# mic_v3.net
KiCad netlist of a schematic drawn in EAGLE
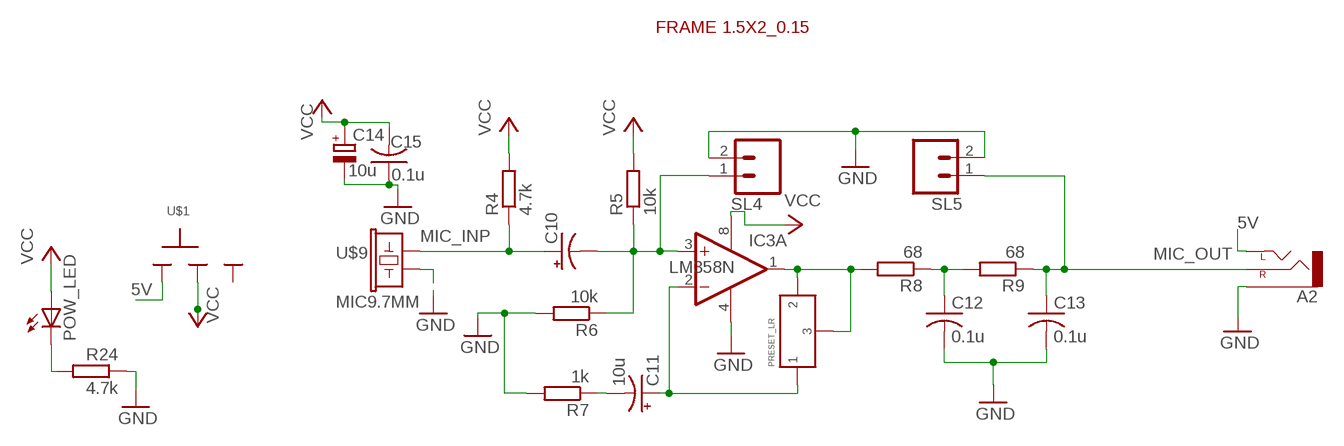
[diagram p0: schematic, sheet 1]

(export (version "E")
  (design (tool "Eeschema 10.0.6"))
  (components
    (comp (ref "A2")
      (value "AUDIO-JACKPTH")
      (footprint "eagle-import:AUDIO-JACK")
      (libsource (lib "eagle-import") (part "AUDIO-JACKPTH"))
    )
    (comp (ref "C10")
      (value "CPOL-USE2.5-5")
      (footprint "eagle-import:E2,5-5")
      (libsource (lib "eagle-import") (part "CPOL-USE2.5-5"))
    )
    (comp (ref "C11")
      (value "10u")
      (footprint "eagle-import:E2,5-5")
      (libsource (lib "eagle-import") (part "CPOL-USE2.5-5"))
    )
    (comp (ref "C12")
      (value "0.1u")
      (footprint "eagle-import:C025-024X044")
      (libsource (lib "eagle-import") (part "C-US025-024X044"))
    )
    (comp (ref "C13")
      (value "0.1u")
      (footprint "eagle-import:C025-024X044")
      (libsource (lib "eagle-import") (part "C-US025-024X044"))
    )
    (comp (ref "C14")
      (value "10u")
      (footprint "eagle-import:E2,5-5")
      (libsource (lib "eagle-import") (part "CPOL-EUE2.5-5"))
    )
    (comp (ref "C15")
      (value "0.1u")
      (footprint "eagle-import:C025-024X044")
      (libsource (lib "eagle-import") (part "C-US025-024X044"))
    )
    (comp (ref "IC3")
      (value "LM358N")
      (footprint "eagle-import:DIL08")
      (libsource (lib "eagle-import") (part "LM358N"))
    )
    (comp (ref "POW_LED")
      (value "LED3MM")
      (footprint "eagle-import:LED3MM")
      (libsource (lib "eagle-import") (part "LED3MM"))
    )
    (comp (ref "R4")
      (value "4.7k")
      (footprint "eagle-import:0204_7")
      (libsource (lib "eagle-import") (part "R-EU_0204/7"))
    )
    (comp (ref "R5")
      (value "10k")
      (footprint "eagle-import:0204_7")
      (libsource (lib "eagle-import") (part "R-EU_0204/7"))
    )
    (comp (ref "R6")
      (value "10k")
      (footprint "eagle-import:0204_7")
      (libsource (lib "eagle-import") (part "R-EU_0204/7"))
    )
    (comp (ref "R7")
      (value "1k")
      (footprint "eagle-import:0204_7")
      (libsource (lib "eagle-import") (part "R-EU_0204/7"))
    )
    (comp (ref "R8")
      (value "68")
      (footprint "eagle-import:0204_7")
      (libsource (lib "eagle-import") (part "R-EU_0204/7"))
    )
    (comp (ref "R9")
      (value "68")
      (footprint "eagle-import:0204_7")
      (libsource (lib "eagle-import") (part "R-EU_0204/7"))
    )
    (comp (ref "R24")
      (value "4.7k")
      (footprint "eagle-import:0204_7")
      (libsource (lib "eagle-import") (part "R-EU_0204/7"))
    )
    (comp (ref "SL4")
      (value "M02")
      (footprint "eagle-import:02P")
      (libsource (lib "eagle-import") (part "M02"))
    )
    (comp (ref "SL5")
      (value "M02")
      (footprint "eagle-import:02P")
      (libsource (lib "eagle-import") (part "M02"))
    )
    (comp (ref "U$1")
      (value "SLIDESWITCH-BIG")
      (footprint "eagle-import:BIGSWITCH")
      (libsource (lib "eagle-import") (part "SLIDESWITCH-BIG"))
    )
    (comp (ref "U$2")
      (value "FRAME_1.5X2_RAD_0.15")
      (footprint "eagle-import:FRAME_1.5X2_RAD_0.15")
      (libsource (lib "eagle-import") (part "FRAME_1.5X2_RAD_0.15"))
    )
    (comp (ref "U$6")
      (value "PRESET_LR")
      (footprint "eagle-import:PRESET_LR")
      (libsource (lib "eagle-import") (part "PRESET_LR"))
    )
    (comp (ref "U$9")
      (value "MIC9.7MM")
      (footprint "eagle-import:MIC-9.7MM")
      (libsource (lib "eagle-import") (part "MIC9.7MM"))
    )
  )
  (nets
    (net (code "1") (name "/5V") (class "Default")
      (node (ref "A2") (pin "TIP") (pinfunction "LEFT_TIP") (pintype "bidirectional"))
      (node (ref "U$1") (pin "1") (pinfunction "1_1") (pintype "bidirectional"))
    )
    (net (code "2") (name "/MIC_INP") (class "Default")
      (node (ref "C10") (pin "+") (pinfunction "+_+") (pintype "passive"))
      (node (ref "R4") (pin "1") (pinfunction "1_1") (pintype "passive"))
      (node (ref "U$9") (pin "1") (pinfunction "1_1") (pintype "passive"))
    )
    (net (code "3") (name "/MIC_OUT") (class "Default")
      (node (ref "A2") (pin "RING") (pinfunction "RIGHT_RING") (pintype "bidirectional"))
      (node (ref "C13") (pin "1") (pinfunction "1_1") (pintype "passive"))
      (node (ref "R9") (pin "1") (pinfunction "1_1") (pintype "passive"))
      (node (ref "SL5") (pin "1") (pinfunction "1_1") (pintype "passive"))
    )
    (net (code "4") (name "GND") (class "Default")
      (node (ref "A2") (pin "SLEEVE") (pinfunction "SLEEVE_SLEEVE") (pintype "bidirectional"))
      (node (ref "C12") (pin "2") (pinfunction "2_2") (pintype "passive"))
      (node (ref "C13") (pin "2") (pinfunction "2_2") (pintype "passive"))
      (node (ref "C14") (pin "-") (pinfunction "-_-") (pintype "passive"))
      (node (ref "C15") (pin "1") (pinfunction "1_1") (pintype "passive"))
      (node (ref "IC3") (pin "4") (pinfunction "V-_4") (pintype "power_in"))
      (node (ref "R24") (pin "1") (pinfunction "1_1") (pintype "passive"))
      (node (ref "R6") (pin "2") (pinfunction "2_2") (pintype "passive"))
      (node (ref "R7") (pin "2") (pinfunction "2_2") (pintype "passive"))
      (node (ref "SL4") (pin "2") (pinfunction "2_2") (pintype "passive"))
      (node (ref "SL5") (pin "2") (pinfunction "2_2") (pintype "passive"))
      (node (ref "U$9") (pin "2") (pinfunction "2_2") (pintype "passive"))
    )
    (net (code "5") (name "Net-(C11-Pad-)") (class "Default")
      (node (ref "C11") (pin "-") (pinfunction "-_-") (pintype "passive"))
      (node (ref "R7") (pin "1") (pinfunction "1_1") (pintype "passive"))
    )
    (net (code "6") (name "Net-(C12-Pad1)") (class "Default")
      (node (ref "C12") (pin "1") (pinfunction "1_1") (pintype "passive"))
      (node (ref "R8") (pin "1") (pinfunction "1_1") (pintype "passive"))
      (node (ref "R9") (pin "2") (pinfunction "2_2") (pintype "passive"))
    )
    (net (code "7") (name "Net-(IC3A-+IN)") (class "Default")
      (node (ref "C10") (pin "-") (pinfunction "-_-") (pintype "passive"))
      (node (ref "IC3") (pin "3") (pinfunction "+IN_3") (pintype "input"))
      (node (ref "R5") (pin "1") (pinfunction "1_1") (pintype "passive"))
      (node (ref "R6") (pin "1") (pinfunction "1_1") (pintype "passive"))
      (node (ref "SL4") (pin "1") (pinfunction "1_1") (pintype "passive"))
    )
    (net (code "8") (name "Net-(IC3A--IN)") (class "Default")
      (node (ref "C11") (pin "+") (pinfunction "+_+") (pintype "passive"))
      (node (ref "IC3") (pin "2") (pinfunction "-IN_2") (pintype "input"))
      (node (ref "U$6") (pin "P$1") (pinfunction "1_P$1") (pintype "passive"))
    )
    (net (code "9") (name "Net-(IC3A-OUT)") (class "Default")
      (node (ref "IC3") (pin "1") (pinfunction "OUT_1") (pintype "output"))
      (node (ref "R8") (pin "2") (pinfunction "2_2") (pintype "passive"))
      (node (ref "U$6") (pin "P$2") (pinfunction "2_P$2") (pintype "passive"))
      (node (ref "U$6") (pin "P$3") (pinfunction "3_P$3") (pintype "passive"))
    )
    (net (code "10") (name "Net-(POW_LED-C)") (class "Default")
      (node (ref "POW_LED") (pin "K") (pinfunction "C_K") (pintype "passive"))
      (node (ref "R24") (pin "2") (pinfunction "2_2") (pintype "passive"))
    )
    (net (code "11") (name "VCC") (class "Default")
      (node (ref "C14") (pin "+") (pinfunction "+_+") (pintype "passive"))
      (node (ref "C15") (pin "2") (pinfunction "2_2") (pintype "passive"))
      (node (ref "IC3") (pin "8") (pinfunction "V+_8") (pintype "power_in"))
      (node (ref "POW_LED") (pin "A") (pinfunction "A_A") (pintype "passive"))
      (node (ref "R4") (pin "2") (pinfunction "2_2") (pintype "passive"))
      (node (ref "R5") (pin "2") (pinfunction "2_2") (pintype "passive"))
      (node (ref "U$1") (pin "2") (pinfunction "2_2") (pintype "bidirectional"))
    )
    (net (code "12") (name "unconnected-(U$1-Pad3)") (class "Default")
      (node (ref "U$1") (pin "3") (pinfunction "3_3") (pintype "bidirectional"))
    )
  )
)
